# expansion_module_sw8_btn4.net
KiCad netlist of a schematic drawn in EAGLE
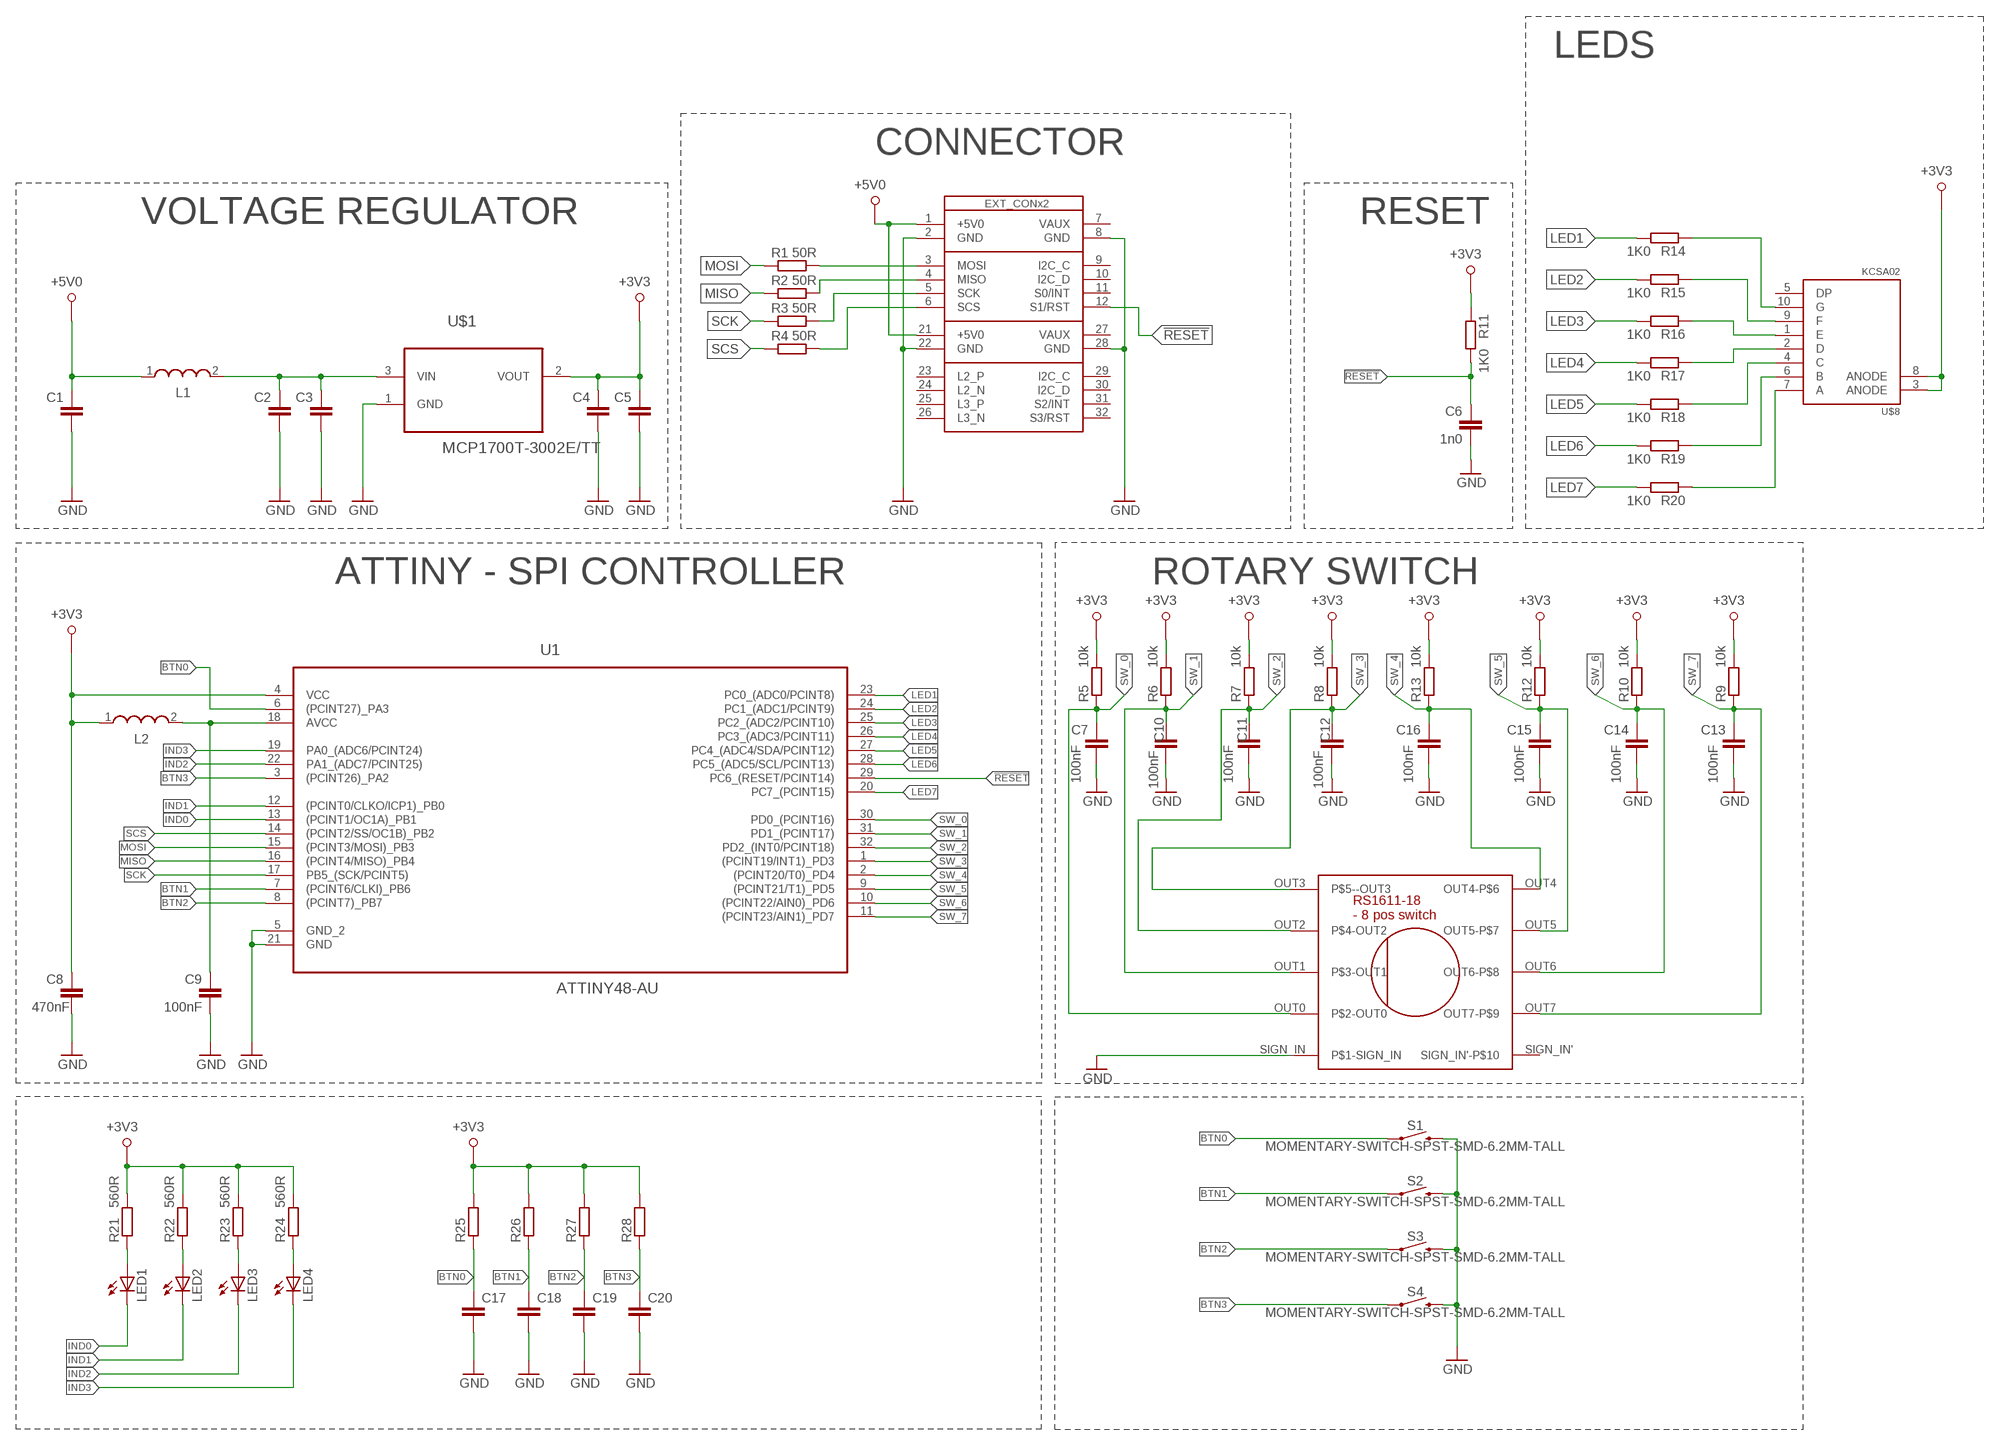
[diagram p0: schematic, sheet 1]

(export (version "E")
  (design (tool "Eeschema 10.0.6"))
  (components
    (comp (ref "C1")
      (value "C-EUC0805")
      (footprint "eagle-import:C0805")
      (libsource (lib "eagle-import") (part "C-EUC0805"))
    )
    (comp (ref "C2")
      (value "C-EUC0805")
      (footprint "eagle-import:C0805")
      (libsource (lib "eagle-import") (part "C-EUC0805"))
    )
    (comp (ref "C3")
      (value "C-EUC0805")
      (footprint "eagle-import:C0805")
      (libsource (lib "eagle-import") (part "C-EUC0805"))
    )
    (comp (ref "C4")
      (value "C-EUC0805")
      (footprint "eagle-import:C0805")
      (libsource (lib "eagle-import") (part "C-EUC0805"))
    )
    (comp (ref "C5")
      (value "C-EUC0805")
      (footprint "eagle-import:C0805")
      (libsource (lib "eagle-import") (part "C-EUC0805"))
    )
    (comp (ref "C6")
      (value "1n0")
      (footprint "eagle-import:C0805")
      (libsource (lib "eagle-import") (part "C-EUC0805"))
    )
    (comp (ref "C7")
      (value "100nF")
      (footprint "eagle-import:C0805")
      (libsource (lib "eagle-import") (part "C-EUC0805"))
    )
    (comp (ref "C8")
      (value "470nF")
      (footprint "eagle-import:C0805")
      (libsource (lib "eagle-import") (part "C-EUC0805"))
    )
    (comp (ref "C9")
      (value "100nF")
      (footprint "eagle-import:C0805")
      (libsource (lib "eagle-import") (part "C-EUC0805"))
    )
    (comp (ref "C10")
      (value "100nF")
      (footprint "eagle-import:C0805")
      (libsource (lib "eagle-import") (part "C-EUC0805"))
    )
    (comp (ref "C11")
      (value "100nF")
      (footprint "eagle-import:C0805")
      (libsource (lib "eagle-import") (part "C-EUC0805"))
    )
    (comp (ref "C12")
      (value "100nF")
      (footprint "eagle-import:C0805")
      (libsource (lib "eagle-import") (part "C-EUC0805"))
    )
    (comp (ref "C13")
      (value "100nF")
      (footprint "eagle-import:C0805")
      (libsource (lib "eagle-import") (part "C-EUC0805"))
    )
    (comp (ref "C14")
      (value "100nF")
      (footprint "eagle-import:C0805")
      (libsource (lib "eagle-import") (part "C-EUC0805"))
    )
    (comp (ref "C15")
      (value "100nF")
      (footprint "eagle-import:C0805")
      (libsource (lib "eagle-import") (part "C-EUC0805"))
    )
    (comp (ref "C16")
      (value "100nF")
      (footprint "eagle-import:C0805")
      (libsource (lib "eagle-import") (part "C-EUC0805"))
    )
    (comp (ref "C17")
      (value "C-EUC0603K")
      (footprint "eagle-import:C0603K")
      (libsource (lib "eagle-import") (part "C-EUC0603K"))
    )
    (comp (ref "C18")
      (value "C-EUC0603K")
      (footprint "eagle-import:C0603K")
      (libsource (lib "eagle-import") (part "C-EUC0603K"))
    )
    (comp (ref "C19")
      (value "C-EUC0603K")
      (footprint "eagle-import:C0603K")
      (libsource (lib "eagle-import") (part "C-EUC0603K"))
    )
    (comp (ref "C20")
      (value "C-EUC0603K")
      (footprint "eagle-import:C0603K")
      (libsource (lib "eagle-import") (part "C-EUC0603K"))
    )
    (comp (ref "L1")
      (value "WE-LQ_1210")
      (footprint "eagle-import:WE-LQ_M")
      (libsource (lib "eagle-import") (part "WE-LQ_1210"))
    )
    (comp (ref "L2")
      (value "WE-PMI_0805")
      (footprint "eagle-import:WE-PMI_0805")
      (libsource (lib "eagle-import") (part "WE-PMI_0805"))
    )
    (comp (ref "LED1")
      (value "LEDCHIPLED_0805")
      (footprint "eagle-import:CHIPLED_0805")
      (libsource (lib "eagle-import") (part "LEDCHIPLED_0805"))
    )
    (comp (ref "LED2")
      (value "LEDCHIPLED_0805")
      (footprint "eagle-import:CHIPLED_0805")
      (libsource (lib "eagle-import") (part "LEDCHIPLED_0805"))
    )
    (comp (ref "LED3")
      (value "LEDCHIPLED_0805")
      (footprint "eagle-import:CHIPLED_0805")
      (libsource (lib "eagle-import") (part "LEDCHIPLED_0805"))
    )
    (comp (ref "LED4")
      (value "LEDCHIPLED_0805")
      (footprint "eagle-import:CHIPLED_0805")
      (libsource (lib "eagle-import") (part "LEDCHIPLED_0805"))
    )
    (comp (ref "R1")
      (value "50R")
      (footprint "eagle-import:R0805")
      (libsource (lib "eagle-import") (part "R-EU_R0805"))
    )
    (comp (ref "R2")
      (value "50R")
      (footprint "eagle-import:R0805")
      (libsource (lib "eagle-import") (part "R-EU_R0805"))
    )
    (comp (ref "R3")
      (value "50R")
      (footprint "eagle-import:R0805")
      (libsource (lib "eagle-import") (part "R-EU_R0805"))
    )
    (comp (ref "R4")
      (value "50R")
      (footprint "eagle-import:R0805")
      (libsource (lib "eagle-import") (part "R-EU_R0805"))
    )
    (comp (ref "R5")
      (value "10k")
      (footprint "eagle-import:R0805")
      (libsource (lib "eagle-import") (part "R-EU_R0805"))
    )
    (comp (ref "R6")
      (value "10k")
      (footprint "eagle-import:R0805")
      (libsource (lib "eagle-import") (part "R-EU_R0805"))
    )
    (comp (ref "R7")
      (value "10k")
      (footprint "eagle-import:R0805")
      (libsource (lib "eagle-import") (part "R-EU_R0805"))
    )
    (comp (ref "R8")
      (value "10k")
      (footprint "eagle-import:R0805")
      (libsource (lib "eagle-import") (part "R-EU_R0805"))
    )
    (comp (ref "R9")
      (value "10k")
      (footprint "eagle-import:R0805")
      (libsource (lib "eagle-import") (part "R-EU_R0805"))
    )
    (comp (ref "R10")
      (value "10k")
      (footprint "eagle-import:R0805")
      (libsource (lib "eagle-import") (part "R-EU_R0805"))
    )
    (comp (ref "R11")
      (value "1K0")
      (footprint "eagle-import:R0805")
      (libsource (lib "eagle-import") (part "R-EU_R0805"))
    )
    (comp (ref "R12")
      (value "10k")
      (footprint "eagle-import:R0805")
      (libsource (lib "eagle-import") (part "R-EU_R0805"))
    )
    (comp (ref "R13")
      (value "10k")
      (footprint "eagle-import:R0805")
      (libsource (lib "eagle-import") (part "R-EU_R0805"))
    )
    (comp (ref "R14")
      (value "1K0")
      (footprint "eagle-import:R0805")
      (libsource (lib "eagle-import") (part "R-EU_R0805"))
    )
    (comp (ref "R15")
      (value "1K0")
      (footprint "eagle-import:R0805")
      (libsource (lib "eagle-import") (part "R-EU_R0805"))
    )
    (comp (ref "R16")
      (value "1K0")
      (footprint "eagle-import:R0805")
      (libsource (lib "eagle-import") (part "R-EU_R0805"))
    )
    (comp (ref "R17")
      (value "1K0")
      (footprint "eagle-import:R0805")
      (libsource (lib "eagle-import") (part "R-EU_R0805"))
    )
    (comp (ref "R18")
      (value "1K0")
      (footprint "eagle-import:R0805")
      (libsource (lib "eagle-import") (part "R-EU_R0805"))
    )
    (comp (ref "R19")
      (value "1K0")
      (footprint "eagle-import:R0805")
      (libsource (lib "eagle-import") (part "R-EU_R0805"))
    )
    (comp (ref "R20")
      (value "1K0")
      (footprint "eagle-import:R0805")
      (libsource (lib "eagle-import") (part "R-EU_R0805"))
    )
    (comp (ref "R21")
      (value "560R")
      (footprint "eagle-import:R0805")
      (libsource (lib "eagle-import") (part "R-EU_R0805"))
    )
    (comp (ref "R22")
      (value "560R")
      (footprint "eagle-import:R0805")
      (libsource (lib "eagle-import") (part "R-EU_R0805"))
    )
    (comp (ref "R23")
      (value "560R")
      (footprint "eagle-import:R0805")
      (libsource (lib "eagle-import") (part "R-EU_R0805"))
    )
    (comp (ref "R24")
      (value "560R")
      (footprint "eagle-import:R0805")
      (libsource (lib "eagle-import") (part "R-EU_R0805"))
    )
    (comp (ref "R25")
      (value "R-EU_R0603")
      (footprint "eagle-import:R0603")
      (libsource (lib "eagle-import") (part "R-EU_R0603"))
    )
    (comp (ref "R26")
      (value "R-EU_R0603")
      (footprint "eagle-import:R0603")
      (libsource (lib "eagle-import") (part "R-EU_R0603"))
    )
    (comp (ref "R27")
      (value "R-EU_R0603")
      (footprint "eagle-import:R0603")
      (libsource (lib "eagle-import") (part "R-EU_R0603"))
    )
    (comp (ref "R28")
      (value "R-EU_R0603")
      (footprint "eagle-import:R0603")
      (libsource (lib "eagle-import") (part "R-EU_R0603"))
    )
    (comp (ref "S1")
      (value "MOMENTARY-SWITCH-SPST-SMD-6.2MM-TALL")
      (footprint "eagle-import:TACTILE_SWITCH_SMD_6.2MM_TALL")
      (libsource (lib "eagle-import") (part "MOMENTARY-SWITCH-SPST-SMD-6.2MM-TALL"))
    )
    (comp (ref "S2")
      (value "MOMENTARY-SWITCH-SPST-SMD-6.2MM-TALL")
      (footprint "eagle-import:TACTILE_SWITCH_SMD_6.2MM_TALL")
      (libsource (lib "eagle-import") (part "MOMENTARY-SWITCH-SPST-SMD-6.2MM-TALL"))
    )
    (comp (ref "S3")
      (value "MOMENTARY-SWITCH-SPST-SMD-6.2MM-TALL")
      (footprint "eagle-import:TACTILE_SWITCH_SMD_6.2MM_TALL")
      (libsource (lib "eagle-import") (part "MOMENTARY-SWITCH-SPST-SMD-6.2MM-TALL"))
    )
    (comp (ref "S4")
      (value "MOMENTARY-SWITCH-SPST-SMD-6.2MM-TALL")
      (footprint "eagle-import:TACTILE_SWITCH_SMD_6.2MM_TALL")
      (libsource (lib "eagle-import") (part "MOMENTARY-SWITCH-SPST-SMD-6.2MM-TALL"))
    )
    (comp (ref "U$1")
      (value "MCP1700T-3002E/TT")
      (footprint "eagle-import:SOT95P237X112-3N")
      (libsource (lib "eagle-import") (part "MCP1700T-3002E/TT"))
    )
    (comp (ref "U$8")
      (value "KCSA02-109-SMALL")
      (footprint "eagle-import:KCSX02-SM")
      (libsource (lib "eagle-import") (part "KCSA02-109-SMALL"))
    )
    (comp (ref "U$20")
      (value "RS1611-18_ROTARY_SW")
      (footprint "eagle-import:RS1611-PACKAGE")
      (libsource (lib "eagle-import") (part "RS1611-18_ROTARY_SW"))
    )
    (comp (ref "U$37")
      (value "SB_EXT_CON_X2_SPI")
      (footprint "eagle-import:SB_EXT_CON_X2_FULL")
      (libsource (lib "eagle-import") (part "SB_EXT_CON_X2_SPI"))
    )
    (comp (ref "U1")
      (value "ATTINY48-AU")
      (footprint "eagle-import:QFP80P900X900X120-32N")
      (libsource (lib "eagle-import") (part "ATTINY48-AU"))
    )
  )
  (nets
    (net (code "1") (name "+3V3") (class "Default")
      (node (ref "C4") (pin "2") (pinfunction "2_2") (pintype "passive"))
      (node (ref "C5") (pin "2") (pinfunction "2_2") (pintype "passive"))
      (node (ref "C8") (pin "2") (pinfunction "2_2") (pintype "passive"))
      (node (ref "L2") (pin "1") (pinfunction "1_1") (pintype "passive"))
      (node (ref "R10") (pin "2") (pinfunction "2_2") (pintype "passive"))
      (node (ref "R11") (pin "1") (pinfunction "1_1") (pintype "passive"))
      (node (ref "R12") (pin "2") (pinfunction "2_2") (pintype "passive"))
      (node (ref "R13") (pin "2") (pinfunction "2_2") (pintype "passive"))
      (node (ref "R21") (pin "2") (pinfunction "2_2") (pintype "passive"))
      (node (ref "R22") (pin "2") (pinfunction "2_2") (pintype "passive"))
      (node (ref "R23") (pin "2") (pinfunction "2_2") (pintype "passive"))
      (node (ref "R24") (pin "2") (pinfunction "2_2") (pintype "passive"))
      (node (ref "R25") (pin "2") (pinfunction "2_2") (pintype "passive"))
      (node (ref "R26") (pin "2") (pinfunction "2_2") (pintype "passive"))
      (node (ref "R27") (pin "2") (pinfunction "2_2") (pintype "passive"))
      (node (ref "R28") (pin "2") (pinfunction "2_2") (pintype "passive"))
      (node (ref "R5") (pin "2") (pinfunction "2_2") (pintype "passive"))
      (node (ref "R6") (pin "2") (pinfunction "2_2") (pintype "passive"))
      (node (ref "R7") (pin "2") (pinfunction "2_2") (pintype "passive"))
      (node (ref "R8") (pin "2") (pinfunction "2_2") (pintype "passive"))
      (node (ref "R9") (pin "2") (pinfunction "2_2") (pintype "passive"))
      (node (ref "U$1") (pin "2") (pinfunction "VOUT_2") (pintype "output"))
      (node (ref "U$8") (pin "3") (pinfunction "ANODE_3") (pintype "bidirectional"))
      (node (ref "U$8") (pin "8") (pinfunction "ANODE_8") (pintype "bidirectional"))
      (node (ref "U1") (pin "4") (pinfunction "VCC_4") (pintype "power_in"))
    )
    (net (code "2") (name "+5V0") (class "Default")
      (node (ref "C1") (pin "2") (pinfunction "2_2") (pintype "passive"))
      (node (ref "L1") (pin "1") (pinfunction "1_1") (pintype "passive"))
      (node (ref "U$37") (pin "1") (pinfunction "+5V0_1") (pintype "bidirectional"))
      (node (ref "U$37") (pin "21") (pinfunction "+5V0_21") (pintype "bidirectional"))
    )
    (net (code "3") (name "/~{RESET}") (class "Default")
      (node (ref "C6") (pin "2") (pinfunction "2_2") (pintype "passive"))
      (node (ref "R11") (pin "2") (pinfunction "2_2") (pintype "passive"))
      (node (ref "U$37") (pin "12") (pinfunction "S1/RST_12") (pintype "bidirectional"))
      (node (ref "U1") (pin "29") (pinfunction "PC6_(RESET/PCINT14)_29") (pintype "bidirectional"))
    )
    (net (code "4") (name "BTN0") (class "Default")
      (node (ref "C17") (pin "1") (pinfunction "1_1") (pintype "passive"))
      (node (ref "R25") (pin "1") (pinfunction "1_1") (pintype "passive"))
      (node (ref "S1") (pin "A2") (pinfunction "1_A2") (pintype "passive"))
      (node (ref "U1") (pin "6") (pinfunction "(PCINT27)_PA3_6") (pintype "bidirectional"))
    )
    (net (code "5") (name "BTN1") (class "Default")
      (node (ref "C18") (pin "1") (pinfunction "1_1") (pintype "passive"))
      (node (ref "R26") (pin "1") (pinfunction "1_1") (pintype "passive"))
      (node (ref "S2") (pin "A2") (pinfunction "1_A2") (pintype "passive"))
      (node (ref "U1") (pin "7") (pinfunction "(PCINT6/CLKI)_PB6_7") (pintype "bidirectional"))
    )
    (net (code "6") (name "BTN2") (class "Default")
      (node (ref "C19") (pin "1") (pinfunction "1_1") (pintype "passive"))
      (node (ref "R27") (pin "1") (pinfunction "1_1") (pintype "passive"))
      (node (ref "S3") (pin "A2") (pinfunction "1_A2") (pintype "passive"))
      (node (ref "U1") (pin "8") (pinfunction "(PCINT7)_PB7_8") (pintype "bidirectional"))
    )
    (net (code "7") (name "BTN3") (class "Default")
      (node (ref "C20") (pin "1") (pinfunction "1_1") (pintype "passive"))
      (node (ref "R28") (pin "1") (pinfunction "1_1") (pintype "passive"))
      (node (ref "S4") (pin "A2") (pinfunction "1_A2") (pintype "passive"))
      (node (ref "U1") (pin "3") (pinfunction "(PCINT26)_PA2_3") (pintype "bidirectional"))
    )
    (net (code "8") (name "GND") (class "Default")
      (node (ref "C1") (pin "1") (pinfunction "1_1") (pintype "passive"))
      (node (ref "C10") (pin "1") (pinfunction "1_1") (pintype "passive"))
      (node (ref "C11") (pin "1") (pinfunction "1_1") (pintype "passive"))
      (node (ref "C12") (pin "1") (pinfunction "1_1") (pintype "passive"))
      (node (ref "C13") (pin "1") (pinfunction "1_1") (pintype "passive"))
      (node (ref "C14") (pin "1") (pinfunction "1_1") (pintype "passive"))
      (node (ref "C15") (pin "1") (pinfunction "1_1") (pintype "passive"))
      (node (ref "C16") (pin "1") (pinfunction "1_1") (pintype "passive"))
      (node (ref "C17") (pin "2") (pinfunction "2_2") (pintype "passive"))
      (node (ref "C18") (pin "2") (pinfunction "2_2") (pintype "passive"))
      (node (ref "C19") (pin "2") (pinfunction "2_2") (pintype "passive"))
      (node (ref "C2") (pin "1") (pinfunction "1_1") (pintype "passive"))
      (node (ref "C20") (pin "2") (pinfunction "2_2") (pintype "passive"))
      (node (ref "C3") (pin "1") (pinfunction "1_1") (pintype "passive"))
      (node (ref "C4") (pin "1") (pinfunction "1_1") (pintype "passive"))
      (node (ref "C5") (pin "1") (pinfunction "1_1") (pintype "passive"))
      (node (ref "C6") (pin "1") (pinfunction "1_1") (pintype "passive"))
      (node (ref "C7") (pin "1") (pinfunction "1_1") (pintype "passive"))
      (node (ref "C8") (pin "1") (pinfunction "1_1") (pintype "passive"))
      (node (ref "C9") (pin "1") (pinfunction "1_1") (pintype "passive"))
      (node (ref "S1") (pin "B2") (pinfunction "2_B2") (pintype "passive"))
      (node (ref "S2") (pin "B2") (pinfunction "2_B2") (pintype "passive"))
      (node (ref "S3") (pin "B2") (pinfunction "2_B2") (pintype "passive"))
      (node (ref "S4") (pin "B2") (pinfunction "2_B2") (pintype "passive"))
      (node (ref "U$1") (pin "1") (pinfunction "GND_1") (pintype "passive"))
      (node (ref "U$20") (pin "SIGN_IN") (pinfunction "P$1-SIGN_IN_SIGN_IN") (pintype "bidirectional"))
      (node (ref "U$37") (pin "2") (pinfunction "GND_2") (pintype "bidirectional"))
      (node (ref "U$37") (pin "22") (pinfunction "GND_22") (pintype "bidirectional"))
      (node (ref "U$37") (pin "28") (pinfunction "GND_28") (pintype "bidirectional"))
      (node (ref "U$37") (pin "8") (pinfunction "GND_8") (pintype "bidirectional"))
      (node (ref "U1") (pin "21") (pinfunction "GND_21") (pintype "passive"))
      (node (ref "U1") (pin "5") (pinfunction "GND_2_5") (pintype "passive"))
    )
    (net (code "9") (name "IND0") (class "Default")
      (node (ref "LED1") (pin "C") (pinfunction "C_C") (pintype "passive"))
      (node (ref "U1") (pin "13") (pinfunction "(PCINT1/OC1A)_PB1_13") (pintype "bidirectional"))
    )
    (net (code "10") (name "IND1") (class "Default")
      (node (ref "LED2") (pin "C") (pinfunction "C_C") (pintype "passive"))
      (node (ref "U1") (pin "12") (pinfunction "(PCINT0/CLKO/ICP1)_PB0_12") (pintype "bidirectional"))
    )
    (net (code "11") (name "IND2") (class "Default")
      (node (ref "LED3") (pin "C") (pinfunction "C_C") (pintype "passive"))
      (node (ref "U1") (pin "22") (pinfunction "PA1_(ADC7/PCINT25)_22") (pintype "bidirectional"))
    )
    (net (code "12") (name "IND3") (class "Default")
      (node (ref "LED4") (pin "C") (pinfunction "C_C") (pintype "passive"))
      (node (ref "U1") (pin "19") (pinfunction "PA0_(ADC6/PCINT24)_19") (pintype "bidirectional"))
    )
    (net (code "13") (name "LED1") (class "Default")
      (node (ref "R14") (pin "2") (pinfunction "2_2") (pintype "passive"))
      (node (ref "U1") (pin "23") (pinfunction "PC0_(ADC0/PCINT8)_23") (pintype "bidirectional"))
    )
    (net (code "14") (name "LED2") (class "Default")
      (node (ref "R15") (pin "2") (pinfunction "2_2") (pintype "passive"))
      (node (ref "U1") (pin "24") (pinfunction "PC1_(ADC1/PCINT9)_24") (pintype "bidirectional"))
    )
    (net (code "15") (name "LED3") (class "Default")
      (node (ref "R16") (pin "2") (pinfunction "2_2") (pintype "passive"))
      (node (ref "U1") (pin "25") (pinfunction "PC2_(ADC2/PCINT10)_25") (pintype "bidirectional"))
    )
    (net (code "16") (name "LED4") (class "Default")
      (node (ref "R17") (pin "2") (pinfunction "2_2") (pintype "passive"))
      (node (ref "U1") (pin "26") (pinfunction "PC3_(ADC3/PCINT11)_26") (pintype "bidirectional"))
    )
    (net (code "17") (name "LED5") (class "Default")
      (node (ref "R18") (pin "2") (pinfunction "2_2") (pintype "passive"))
      (node (ref "U1") (pin "27") (pinfunction "PC4_(ADC4/SDA/PCINT12)_27") (pintype "bidirectional"))
    )
    (net (code "18") (name "LED6") (class "Default")
      (node (ref "R19") (pin "2") (pinfunction "2_2") (pintype "passive"))
      (node (ref "U1") (pin "28") (pinfunction "PC5_(ADC5/SCL/PCINT13)_28") (pintype "bidirectional"))
    )
    (net (code "19") (name "LED7") (class "Default")
      (node (ref "R20") (pin "2") (pinfunction "2_2") (pintype "passive"))
      (node (ref "U1") (pin "20") (pinfunction "PC7_(PCINT15)_20") (pintype "bidirectional"))
    )
    (net (code "20") (name "MISO") (class "Default")
      (node (ref "R2") (pin "1") (pinfunction "1_1") (pintype "passive"))
      (node (ref "U1") (pin "16") (pinfunction "(PCINT4/MISO)_PB4_16") (pintype "bidirectional"))
    )
    (net (code "21") (name "MOSI") (class "Default")
      (node (ref "R1") (pin "1") (pinfunction "1_1") (pintype "passive"))
      (node (ref "U1") (pin "15") (pinfunction "(PCINT3/MOSI)_PB3_15") (pintype "bidirectional"))
    )
    (net (code "22") (name "Net-(LED1-PadA)") (class "Default")
      (node (ref "LED1") (pin "A") (pinfunction "A_A") (pintype "passive"))
      (node (ref "R21") (pin "1") (pinfunction "1_1") (pintype "passive"))
    )
    (net (code "23") (name "Net-(LED2-PadA)") (class "Default")
      (node (ref "LED2") (pin "A") (pinfunction "A_A") (pintype "passive"))
      (node (ref "R22") (pin "1") (pinfunction "1_1") (pintype "passive"))
    )
    (net (code "24") (name "Net-(LED3-PadA)") (class "Default")
      (node (ref "LED3") (pin "A") (pinfunction "A_A") (pintype "passive"))
      (node (ref "R23") (pin "1") (pinfunction "1_1") (pintype "passive"))
    )
    (net (code "25") (name "Net-(LED4-PadA)") (class "Default")
      (node (ref "LED4") (pin "A") (pinfunction "A_A") (pintype "passive"))
      (node (ref "R24") (pin "1") (pinfunction "1_1") (pintype "passive"))
    )
    (net (code "26") (name "Net-(U$1-VIN)") (class "Default")
      (node (ref "C2") (pin "2") (pinfunction "2_2") (pintype "passive"))
      (node (ref "C3") (pin "2") (pinfunction "2_2") (pintype "passive"))
      (node (ref "L1") (pin "2") (pinfunction "2_2") (pintype "passive"))
      (node (ref "U$1") (pin "3") (pinfunction "VIN_3") (pintype "input"))
    )
    (net (code "27") (name "Net-(U$8-A)") (class "Default")
      (node (ref "R20") (pin "1") (pinfunction "1_1") (pintype "passive"))
      (node (ref "U$8") (pin "7") (pinfunction "A_7") (pintype "bidirectional"))
    )
    (net (code "28") (name "Net-(U$8-B)") (class "Default")
      (node (ref "R19") (pin "1") (pinfunction "1_1") (pintype "passive"))
      (node (ref "U$8") (pin "6") (pinfunction "B_6") (pintype "bidirectional"))
    )
    (net (code "29") (name "Net-(U$8-C)") (class "Default")
      (node (ref "R18") (pin "1") (pinfunction "1_1") (pintype "passive"))
      (node (ref "U$8") (pin "4") (pinfunction "C_4") (pintype "bidirectional"))
    )
    (net (code "30") (name "Net-(U$8-D)") (class "Default")
      (node (ref "R17") (pin "1") (pinfunction "1_1") (pintype "passive"))
      (node (ref "U$8") (pin "2") (pinfunction "D_2") (pintype "bidirectional"))
    )
    (net (code "31") (name "Net-(U$8-E)") (class "Default")
      (node (ref "R16") (pin "1") (pinfunction "1_1") (pintype "passive"))
      (node (ref "U$8") (pin "1") (pinfunction "E_1") (pintype "bidirectional"))
    )
    (net (code "32") (name "Net-(U$8-F)") (class "Default")
      (node (ref "R15") (pin "1") (pinfunction "1_1") (pintype "passive"))
      (node (ref "U$8") (pin "9") (pinfunction "F_9") (pintype "bidirectional"))
    )
    (net (code "33") (name "Net-(U$8-G)") (class "Default")
      (node (ref "R14") (pin "1") (pinfunction "1_1") (pintype "passive"))
      (node (ref "U$8") (pin "10") (pinfunction "G_10") (pintype "bidirectional"))
    )
    (net (code "34") (name "Net-(U$37-MISO)") (class "Default")
      (node (ref "R2") (pin "2") (pinfunction "2_2") (pintype "passive"))
      (node (ref "U$37") (pin "4") (pinfunction "MISO_4") (pintype "bidirectional"))
    )
    (net (code "35") (name "Net-(U$37-MOSI)") (class "Default")
      (node (ref "R1") (pin "2") (pinfunction "2_2") (pintype "passive"))
      (node (ref "U$37") (pin "3") (pinfunction "MOSI_3") (pintype "bidirectional"))
    )
    (net (code "36") (name "Net-(U$37-SCK)") (class "Default")
      (node (ref "R3") (pin "2") (pinfunction "2_2") (pintype "passive"))
      (node (ref "U$37") (pin "5") (pinfunction "SCK_5") (pintype "bidirectional"))
    )
    (net (code "37") (name "Net-(U$37-SCS)") (class "Default")
      (node (ref "R4") (pin "2") (pinfunction "2_2") (pintype "passive"))
      (node (ref "U$37") (pin "6") (pinfunction "SCS_6") (pintype "bidirectional"))
    )
    (net (code "38") (name "Net-(U1-AVCC)") (class "Default")
      (node (ref "C9") (pin "2") (pinfunction "2_2") (pintype "passive"))
      (node (ref "L2") (pin "2") (pinfunction "2_2") (pintype "passive"))
      (node (ref "U1") (pin "18") (pinfunction "AVCC_18") (pintype "power_in"))
    )
    (net (code "39") (name "SCK") (class "Default")
      (node (ref "R3") (pin "1") (pinfunction "1_1") (pintype "passive"))
      (node (ref "U1") (pin "17") (pinfunction "PB5_(SCK/PCINT5)_17") (pintype "bidirectional"))
    )
    (net (code "40") (name "SCS") (class "Default")
      (node (ref "R4") (pin "1") (pinfunction "1_1") (pintype "passive"))
      (node (ref "U1") (pin "14") (pinfunction "(PCINT2/SS/OC1B)_PB2_14") (pintype "bidirectional"))
    )
    (net (code "41") (name "SW_0") (class "Default")
      (node (ref "C7") (pin "2") (pinfunction "2_2") (pintype "passive"))
      (node (ref "R5") (pin "1") (pinfunction "1_1") (pintype "passive"))
      (node (ref "U$20") (pin "OUT0") (pinfunction "P$2-OUT0_OUT0") (pintype "bidirectional"))
      (node (ref "U1") (pin "30") (pinfunction "PD0_(PCINT16)_30") (pintype "bidirectional"))
    )
    (net (code "42") (name "SW_1") (class "Default")
      (node (ref "C10") (pin "2") (pinfunction "2_2") (pintype "passive"))
      (node (ref "R6") (pin "1") (pinfunction "1_1") (pintype "passive"))
      (node (ref "U$20") (pin "OUT1") (pinfunction "P$3-OUT1_OUT1") (pintype "bidirectional"))
      (node (ref "U1") (pin "31") (pinfunction "PD1_(PCINT17)_31") (pintype "bidirectional"))
    )
    (net (code "43") (name "SW_2") (class "Default")
      (node (ref "C11") (pin "2") (pinfunction "2_2") (pintype "passive"))
      (node (ref "R7") (pin "1") (pinfunction "1_1") (pintype "passive"))
      (node (ref "U$20") (pin "OUT2") (pinfunction "P$4-OUT2_OUT2") (pintype "bidirectional"))
      (node (ref "U1") (pin "32") (pinfunction "PD2_(INT0/PCINT18)_32") (pintype "bidirectional"))
    )
    (net (code "44") (name "SW_3") (class "Default")
      (node (ref "C12") (pin "2") (pinfunction "2_2") (pintype "passive"))
      (node (ref "R8") (pin "1") (pinfunction "1_1") (pintype "passive"))
      (node (ref "U$20") (pin "OUT3") (pinfunction "P$5--OUT3_OUT3") (pintype "bidirectional"))
      (node (ref "U1") (pin "1") (pinfunction "(PCINT19/INT1)_PD3_1") (pintype "bidirectional"))
    )
    (net (code "45") (name "SW_4") (class "Default")
      (node (ref "C16") (pin "2") (pinfunction "2_2") (pintype "passive"))
      (node (ref "R13") (pin "1") (pinfunction "1_1") (pintype "passive"))
      (node (ref "U$20") (pin "OUT4") (pinfunction "OUT4-P$6_OUT4") (pintype "bidirectional"))
      (node (ref "U1") (pin "2") (pinfunction "(PCINT20/T0)_PD4_2") (pintype "bidirectional"))
    )
    (net (code "46") (name "SW_5") (class "Default")
      (node (ref "C15") (pin "2") (pinfunction "2_2") (pintype "passive"))
      (node (ref "R12") (pin "1") (pinfunction "1_1") (pintype "passive"))
      (node (ref "U$20") (pin "OUT5") (pinfunction "OUT5-P$7_OUT5") (pintype "bidirectional"))
      (node (ref "U1") (pin "9") (pinfunction "(PCINT21/T1)_PD5_9") (pintype "bidirectional"))
    )
    (net (code "47") (name "SW_6") (class "Default")
      (node (ref "C14") (pin "2") (pinfunction "2_2") (pintype "passive"))
      (node (ref "R10") (pin "1") (pinfunction "1_1") (pintype "passive"))
      (node (ref "U$20") (pin "OUT6") (pinfunction "OUT6-P$8_OUT6") (pintype "bidirectional"))
      (node (ref "U1") (pin "10") (pinfunction "(PCINT22/AIN0)_PD6_10") (pintype "bidirectional"))
    )
    (net (code "48") (name "SW_7") (class "Default")
      (node (ref "C13") (pin "2") (pinfunction "2_2") (pintype "passive"))
      (node (ref "R9") (pin "1") (pinfunction "1_1") (pintype "passive"))
      (node (ref "U$20") (pin "OUT7") (pinfunction "OUT7-P$9_OUT7") (pintype "bidirectional"))
      (node (ref "U1") (pin "11") (pinfunction "(PCINT23/AIN1)_PD7_11") (pintype "bidirectional"))
    )
    (net (code "49") (name "unconnected-(U$8-DP-Pad5)") (class "Default")
      (node (ref "U$8") (pin "5") (pinfunction "DP_5") (pintype "bidirectional"))
    )
    (net (code "50") (name "unconnected-(U$20-SIGN_IN'-P$10-PadSIGN_IN')") (class "Default")
      (node (ref "U$20") (pin "SIGN_IN'") (pinfunction "SIGN_IN'-P$10_SIGN_IN'") (pintype "bidirectional"))
    )
    (net (code "51") (name "unconnected-(U$37-I2C_C-Pad9)") (class "Default")
      (node (ref "U$37") (pin "9") (pinfunction "I2C_C_9") (pintype "bidirectional"))
    )
    (net (code "52") (name "unconnected-(U$37-I2C_C-Pad29)") (class "Default")
      (node (ref "U$37") (pin "29") (pinfunction "I2C_C_29") (pintype "bidirectional"))
    )
    (net (code "53") (name "unconnected-(U$37-I2C_D-Pad10)") (class "Default")
      (node (ref "U$37") (pin "10") (pinfunction "I2C_D_10") (pintype "bidirectional"))
    )
    (net (code "54") (name "unconnected-(U$37-I2C_D-Pad30)") (class "Default")
      (node (ref "U$37") (pin "30") (pinfunction "I2C_D_30") (pintype "bidirectional"))
    )
    (net (code "55") (name "unconnected-(U$37-L2_N-Pad24)") (class "Default")
      (node (ref "U$37") (pin "24") (pinfunction "L2_N_24") (pintype "bidirectional"))
    )
    (net (code "56") (name "unconnected-(U$37-L2_P-Pad23)") (class "Default")
      (node (ref "U$37") (pin "23") (pinfunction "L2_P_23") (pintype "bidirectional"))
    )
    (net (code "57") (name "unconnected-(U$37-L3_N-Pad26)") (class "Default")
      (node (ref "U$37") (pin "26") (pinfunction "L3_N_26") (pintype "bidirectional"))
    )
    (net (code "58") (name "unconnected-(U$37-L3_P-Pad25)") (class "Default")
      (node (ref "U$37") (pin "25") (pinfunction "L3_P_25") (pintype "bidirectional"))
    )
    (net (code "59") (name "unconnected-(U$37-S0{slash}INT-Pad11)") (class "Default")
      (node (ref "U$37") (pin "11") (pinfunction "S0/INT_11") (pintype "bidirectional"))
    )
    (net (code "60") (name "unconnected-(U$37-S2{slash}INT-Pad31)") (class "Default")
      (node (ref "U$37") (pin "31") (pinfunction "S2/INT_31") (pintype "bidirectional"))
    )
    (net (code "61") (name "unconnected-(U$37-S3{slash}RST-Pad32)") (class "Default")
      (node (ref "U$37") (pin "32") (pinfunction "S3/RST_32") (pintype "bidirectional"))
    )
    (net (code "62") (name "unconnected-(U$37-VAUX-Pad7)") (class "Default")
      (node (ref "U$37") (pin "7") (pinfunction "VAUX_7") (pintype "bidirectional"))
    )
    (net (code "63") (name "unconnected-(U$37-VAUX-Pad27)") (class "Default")
      (node (ref "U$37") (pin "27") (pinfunction "VAUX_27") (pintype "bidirectional"))
    )
  )
)
